# theremin.net
KiCad netlist of a schematic drawn in Altium Designer
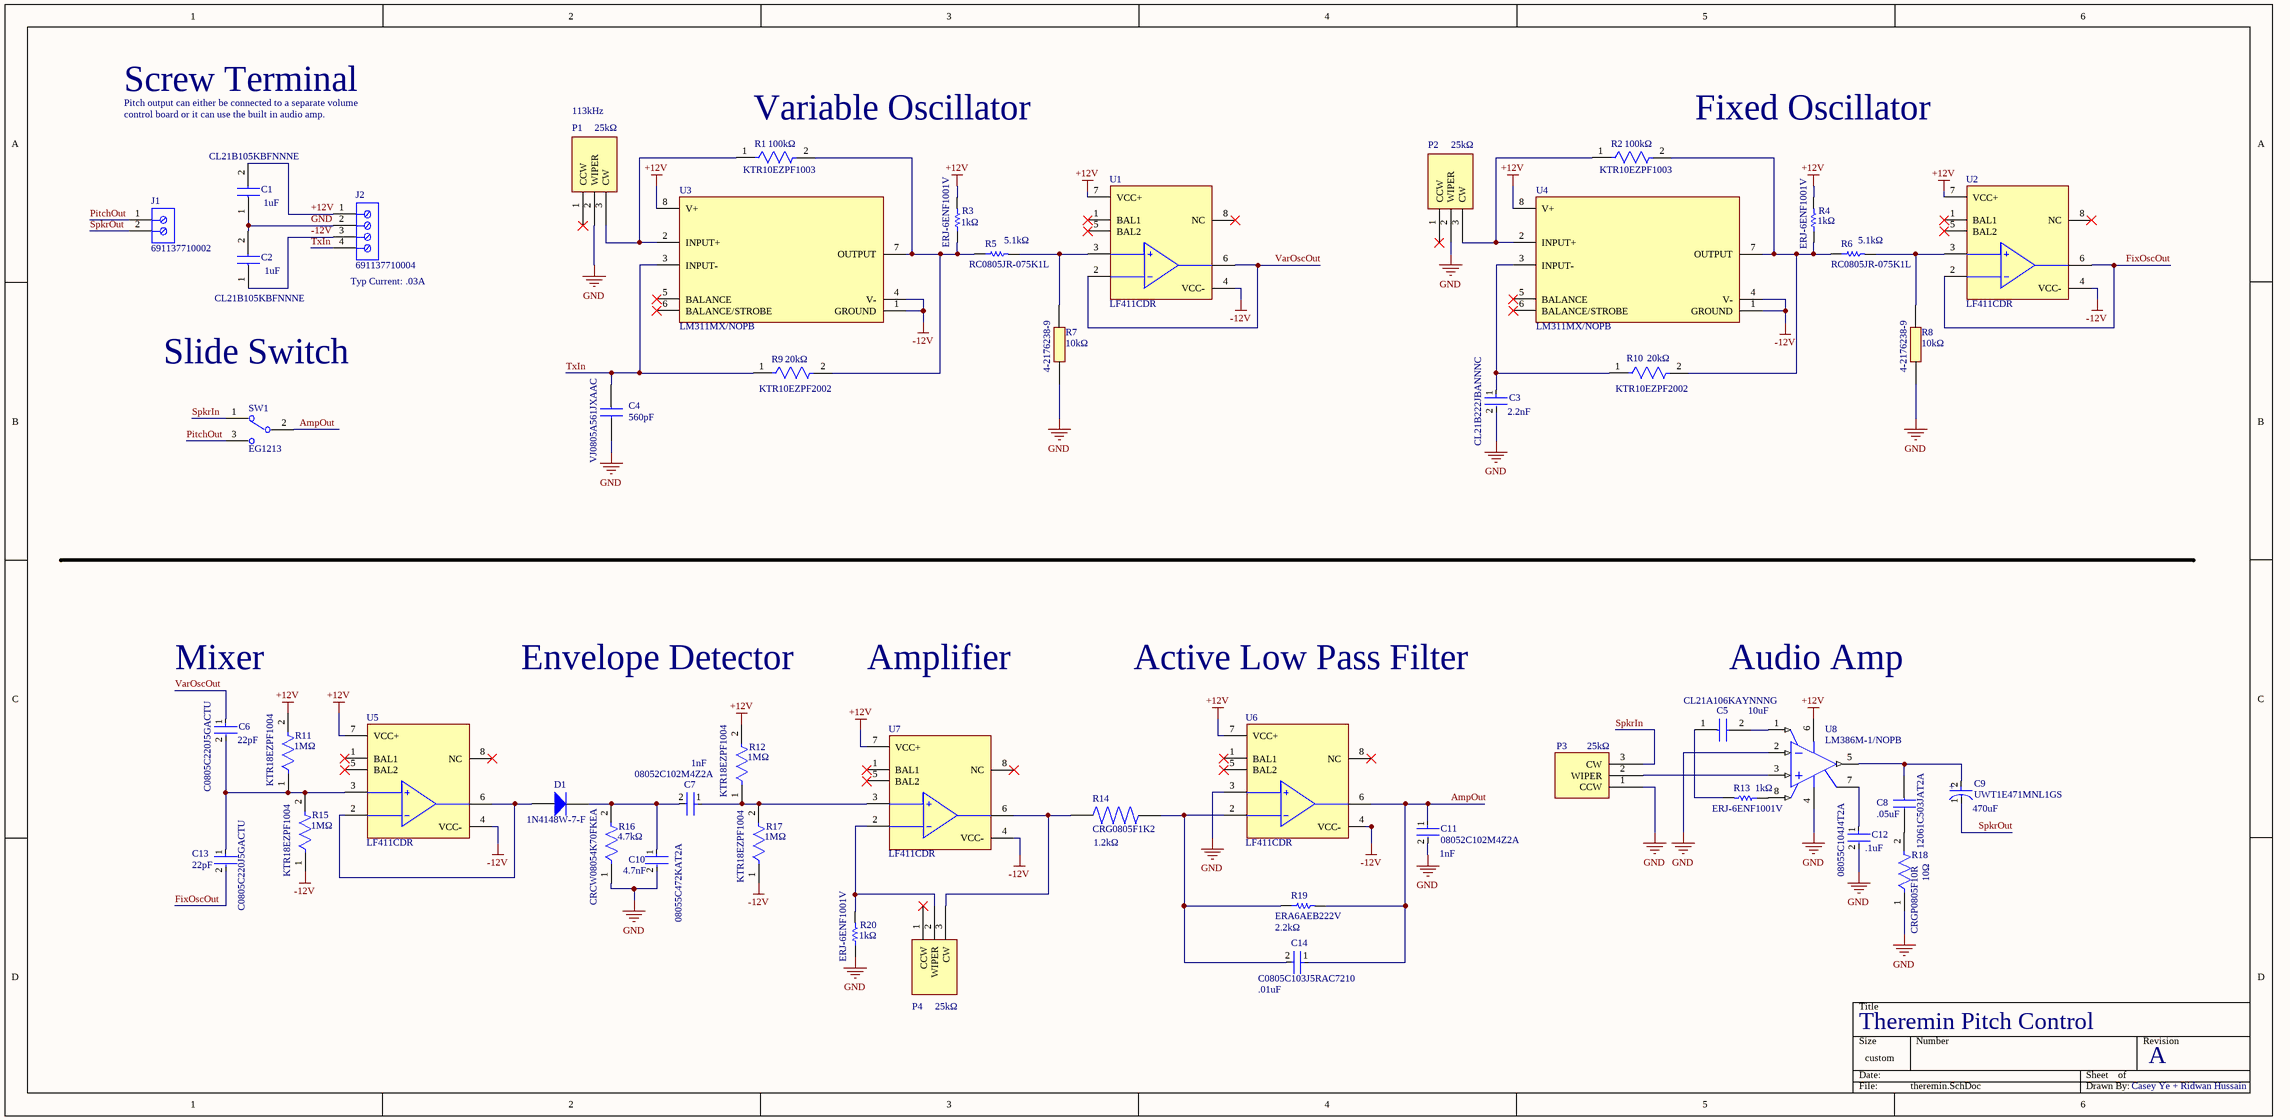
[diagram p0: theremin.SchDoc]

(export (version "E")
  (design (tool "Eeschema 10.0.6"))
  (components
    (comp (ref "C1")
      (value "CL21B105KBFNNNE")
      (footprint "SamacSys:CAPC2012X135N")
      (description "Capacitor")
      (fields (field (name "MOUSER PART NUMBER") "187-CL21B105KBFNNNE"))
      (libsource (lib "*") (part "CL21B105KBFNNNE"))
    )
    (comp (ref "C2")
      (value "CL21B105KBFNNNE")
      (footprint "SamacSys:CAPC2012X135N")
      (description "Capacitor")
      (fields (field (name "MOUSER PART NUMBER") "187-CL21B105KBFNNNE"))
      (libsource (lib "*") (part "CL21B105KBFNNNE"))
    )
    (comp (ref "C3")
      (value "CL21B222JBANNNC")
      (footprint "FP-CL21-IPC_B")
      (description "CL21 Series 0805 2.2nF 50V ±5% Tolerance X7R Multilayer Ceramic Chip Capacitor")
      (fields (field (name "TOLERANCE") "5%") (field (name "VOLTAGE") "50V"))
      (libsource (lib "Altium Content Vault") (part "b4654b650e69147ec39a6b967a45e02"))
    )
    (comp (ref "C4")
      (value "VJ0805A561JXAAC")
      (footprint "CAPC2012X145N")
      (description "VISHAY - VJ0805A561JXAAC - CAP, 560PF, 50V, 5%, C0G/NP0, 0805")
      (fields (field (name "MOUSER PART NUMBER") "77-VJ0805A561JXAAC"))
      (libsource (lib "PCB Lab - Cooper Union") (part "VJ0805A561JXAAC"))
    )
    (comp (ref "C5")
      (value "CL21A106KAYNNNG")
      (footprint "SamacSys:CAPC2012X145N")
      (description "Capacitor")
      (fields (field (name "MOUSER PART NUMBER") "187-CL21A106KAYNNNG"))
      (libsource (lib "*") (part "CL21A106KAYNNNG"))
    )
    (comp (ref "C6")
      (value "C0805C220J5GACTU")
      (footprint "FP-C0805C-DN-MFG")
      (description "Capacitor; Ceramic; Cap; 22.0pF; Tol 5%; SMT; Vol-Rtg 50V; C0G; Tape and Reel")
      (fields
        (field (name "OCTOPART") "https://octopart.com/c0805c220j5gactu-kemet-145470")
        (field (name "MANUFACTURER") "KEMET")
      )
      (libsource (lib "Altium Content Vault") (part "b4654b650e69147ec39a6b967a45e02"))
    )
    (comp (ref "C7")
      (value "08052C102M4Z2A")
      (footprint "FP-0805-L_2_01_0_2-W_1_25-IPC_B")
      (description "Automotive Ceramic Capacitor, 0805, 1nF, 20%, X7R, 0.15, 200V")
      (fields (field (name "TOLERANCE") "20%"))
      (libsource (lib "Altium Content Vault") (part "02cd4be3c70576c341d710602a673aa"))
    )
    (comp (ref "C8")
      (value "12061C503JAT2A")
      (footprint "CAPC3216X94N")
      (description "Multilayer Ceramic Capacitors MLCC - SMD/SMT 100V .05uF X7R 1206 5% Tol")
      (fields (field (name "MOUSER PART NUMBER") "581-12061C503JAT2A"))
      (libsource (lib "PCB Lab - Cooper Union") (part "12061C503JAT2A"))
    )
    (comp (ref "C9")
      (value "UWT1E471MNL1GS")
      (footprint "FP-UWT1E471MNL1GS-MFG")
      (description "CAP ALUM 470UF 20% 25V SMD")
      (fields (field (name "VOLTAGE") "25V") (field (name "TOLERANCE") "20%"))
      (libsource (lib "Altium Content Vault") (part "203bc49f2ac43e59fd269a8c329ed05"))
    )
    (comp (ref "C10")
      (value "08055C472KAT2A")
      (footprint "FP-0805-L_2_01_0_2-W_1_25-IPC_B")
      (description "General Purpose Ceramic Capacitor, 0805, 4.7nF, 10%, X7R, 0.15, 50V")
      (fields (field (name "VOLTAGE") "50V") (field (name "TOLERANCE") "10%"))
      (libsource (lib "Altium Content Vault") (part "02cd4be3c70576c341d710602a673aa"))
    )
    (comp (ref "C11")
      (value "08052C102M4Z2A")
      (footprint "FP-0805-L_2_01_0_2-W_1_25-IPC_B")
      (description "Automotive Ceramic Capacitor, 0805, 1nF, 20%, X7R, 0.15, 200V")
      (fields (field (name "TOLERANCE") "20%"))
      (libsource (lib "Altium Content Vault") (part "02cd4be3c70576c341d710602a673aa"))
    )
    (comp (ref "C12")
      (value "08055C104J4T2A")
      (footprint "FP-0805-L_2_01_0_2-W_1_25-MFG")
      (description "Automotive Ceramic Capacitor, 0805, 100nF, 5%, X7R, 15%, 50V")
      (fields (field (name "TOLERANCE") "5%"))
      (libsource (lib "Altium Content Vault") (part "02cd4be3c70576c341d710602a673aa"))
    )
    (comp (ref "C13")
      (value "C0805C220J5GACTU")
      (footprint "FP-C0805C-DN-MFG")
      (description "Capacitor; Ceramic; Cap; 22.0pF; Tol 5%; SMT; Vol-Rtg 50V; C0G; Tape and Reel")
      (fields
        (field (name "OCTOPART") "https://octopart.com/c0805c220j5gactu-kemet-145470")
        (field (name "MANUFACTURER") "KEMET")
      )
      (libsource (lib "Altium Content Vault") (part "b4654b650e69147ec39a6b967a45e02"))
    )
    (comp (ref "C14")
      (value "C0805C103J5RAC7210")
      (footprint "FP-C0805C-DN-MFG")
      (description "CAP CER SMD 0805 .01UF X7R 5% 50")
      (fields
        (field (name "MANUFACTURER") "KEMET")
        (field (name "OCTOPART") "https://octopart.com/c0805c103j5rac7210-kemet-3921106")
      )
      (libsource (lib "Altium Content Vault") (part "b4654b650e69147ec39a6b967a45e02"))
    )
    (comp (ref "D1")
      (value "1N4148W-7-F")
      (footprint "DIOD-SOD123-2_V")
      (description "Fast Switching Diode, 100 V, 0.15 A, -65 to 150 degC, 2-Pin?SOD123, RoHS, Tape and Reel")
      (fields (field (name "MANUFACTURER") "DiodesIncorporated"))
      (libsource (lib "Altium Content Vault") (part "D-AK-2"))
    )
    (comp (ref "J1")
      (value "691137710002")
      (footprint "691137710002")
      (libsource (lib "Altium Content Vault") (part "TBL - 1R - 02P - Screw"))
    )
    (comp (ref "J2")
      (value "691137710004")
      (footprint "691137710004")
      (libsource (lib "Altium Content Vault") (part "TBL - 1R - 04P - Screw"))
    )
    (comp (ref "P1")
      (value "25kOhmPotentiometer")
      (footprint "25kOhmPotentiometer-Footprint-1")
      (description "25k Ohm Potentiometer")
      (libsource (lib "") (part "25kOhmPotentiometer_1"))
    )
    (comp (ref "P2")
      (value "25kOhmPotentiometer")
      (footprint "25kOhmPotentiometer-Footprint-1")
      (description "25k Ohm Potentiometer")
      (libsource (lib "") (part "25kOhmPotentiometer_1"))
    )
    (comp (ref "P3")
      (value "25kOhmPotentiometer")
      (footprint "25kOhmPotentiometer-Footprint-1")
      (description "25k Ohm Potentiometer")
      (libsource (lib "PCB Lab - Cooper Union") (part "25kOhmPotentiometer"))
    )
    (comp (ref "P4")
      (value "25kOhmPotentiometer")
      (footprint "25kOhmPotentiometer-Footprint-1")
      (description "25k Ohm Potentiometer")
      (libsource (lib "PCB Lab - Cooper Union") (part "25kOhmPotentiometer"))
    )
    (comp (ref "R1")
      (value "KTR10EZPF1003")
      (footprint "FP-KTR10-MFG")
      (description "Res Thick Film 0805 100kΩ 1% 0.125W ±100ppm/°C Automotive Paper T/R")
      (fields (field (name "TOLERANCE") "1%"))
      (libsource (lib "Altium Content Vault") (part "1029c3af85768c4190bb7ad29bc67b5"))
    )
    (comp (ref "R2")
      (value "KTR10EZPF1003")
      (footprint "FP-KTR10-MFG")
      (description "Res Thick Film 0805 100kΩ 1% 0.125W ±100ppm/°C Automotive Paper T/R")
      (fields (field (name "TOLERANCE") "1%"))
      (libsource (lib "Altium Content Vault") (part "1029c3af85768c4190bb7ad29bc67b5"))
    )
    (comp (ref "R3")
      (value "ERJ-6ENF1001V")
      (footprint "RESC2013X70X40ML20T20")
      (description "Chip Resistor, 1 KOhm, +/- 1%, 0.125 W, -55 to 155 degC, 0805 (2012 Metric), RoHS, Tape and Reel")
      (fields (field (name "MANUFACTURER") "Panasonic"))
      (libsource (lib "Altium Content Vault") (part "RES-2"))
    )
    (comp (ref "R4")
      (value "ERJ-6ENF1001V")
      (footprint "RESC2013X70X40ML20T20")
      (description "Chip Resistor, 1 KOhm, +/- 1%, 0.125 W, -55 to 155 degC, 0805 (2012 Metric), RoHS, Tape and Reel")
      (fields (field (name "MANUFACTURER") "Panasonic"))
      (libsource (lib "Altium Content Vault") (part "RES-2"))
    )
    (comp (ref "R5")
      (value "RC0805JR-075K1L")
      (footprint "RESC2013X60X35ML10T20")
      (fields (field (name "MANUFACTURER") "Yageo"))
      (libsource (lib "Altium Content Vault") (part "RES"))
    )
    (comp (ref "R6")
      (value "RC0805JR-075K1L")
      (footprint "RESC2013X60X35ML10T20")
      (fields (field (name "MANUFACTURER") "Yageo"))
      (libsource (lib "Altium Content Vault") (part "RES"))
    )
    (comp (ref "R7")
      (value "4-2176238-9")
      (footprint "RESC2012X65N")
      (description "Thin Film Resistors - SMD CPF A 0805 10K 0.1% 25PPM 5K RL")
      (libsource (lib "PCB Lab - Cooper Union") (part "4-2176238-9"))
    )
    (comp (ref "R8")
      (value "4-2176238-9")
      (footprint "RESC2012X65N")
      (description "Thin Film Resistors - SMD CPF A 0805 10K 0.1% 25PPM 5K RL")
      (libsource (lib "PCB Lab - Cooper Union") (part "4-2176238-9"))
    )
    (comp (ref "R9")
      (value "KTR10EZPF2002")
      (footprint "FP-KTR10-IPC_C")
      (description "Res Thick Film 0805 20kΩ 1% 0.125W ±100ppm/°C Automotive Paper T/R")
      (fields (field (name "TOLERANCE") "1%"))
      (libsource (lib "Altium Content Vault") (part "1029c3af85768c4190bb7ad29bc67b5"))
    )
    (comp (ref "R10")
      (value "KTR10EZPF2002")
      (footprint "FP-KTR10-IPC_C")
      (description "Res Thick Film 0805 20kΩ 1% 0.125W ±100ppm/°C Automotive Paper T/R")
      (fields (field (name "TOLERANCE") "1%"))
      (libsource (lib "Altium Content Vault") (part "1029c3af85768c4190bb7ad29bc67b5"))
    )
    (comp (ref "R11")
      (value "KTR18EZPF1004")
      (footprint "FP-KTR18-IPC_C")
      (description "Res Thick Film 1206 1MΩ 1% 0.1W ±100ppm/°C Automotive Paper T/R")
      (fields (field (name "TOLERANCE") "1%"))
      (libsource (lib "Altium Content Vault") (part "1029c3af85768c4190bb7ad29bc67b5"))
    )
    (comp (ref "R12")
      (value "KTR18EZPF1004")
      (footprint "FP-KTR18-IPC_C")
      (description "Res Thick Film 1206 1MΩ 1% 0.1W ±100ppm/°C Automotive Paper T/R")
      (fields (field (name "TOLERANCE") "1%"))
      (libsource (lib "Altium Content Vault") (part "1029c3af85768c4190bb7ad29bc67b5"))
    )
    (comp (ref "R13")
      (value "ERJ-6ENF1001V")
      (footprint "RESC2013X70X40ML20T20")
      (description "Chip Resistor, 1 KOhm, +/- 1%, 0.125 W, -55 to 155 degC, 0805 (2012 Metric), RoHS, Tape and Reel")
      (fields (field (name "MANUFACTURER") "Panasonic"))
      (libsource (lib "Altium Content Vault") (part "RES-2"))
    )
    (comp (ref "R14")
      (value "CRG0805F1K2")
      (footprint "RESC2012X65N")
      (description "Fixed Resistors")
      (fields (field (name "MF") "TE Connectivity") (field (name "TOLERANCE") "1%"))
      (libsource (lib "PCB Lab - Cooper Union") (part "CRG0805F1K2"))
    )
    (comp (ref "R15")
      (value "KTR18EZPF1004")
      (footprint "FP-KTR18-IPC_C")
      (description "Res Thick Film 1206 1MΩ 1% 0.1W ±100ppm/°C Automotive Paper T/R")
      (fields (field (name "TOLERANCE") "1%"))
      (libsource (lib "Altium Content Vault") (part "1029c3af85768c4190bb7ad29bc67b5"))
    )
    (comp (ref "R16")
      (value "CRCW08054K70FKEA")
      (footprint "FP-CRCW0805-e3-IPC_B")
      (description "RES Thick Film, 4.7kΩ, 1%, 0.125W, 100ppm/°C, 0805")
      (fields (field (name "TOLERANCE") "1%"))
      (libsource (lib "Altium Content Vault") (part "1029c3af85768c4190bb7ad29bc67b5"))
    )
    (comp (ref "R17")
      (value "KTR18EZPF1004")
      (footprint "FP-KTR18-IPC_C")
      (description "Res Thick Film 1206 1MΩ 1% 0.1W ±100ppm/°C Automotive Paper T/R")
      (fields (field (name "TOLERANCE") "1%"))
      (libsource (lib "Altium Content Vault") (part "1029c3af85768c4190bb7ad29bc67b5"))
    )
    (comp (ref "R18")
      (value "CRGP0805F10R")
      (footprint "FP-CRGP0805-IPC_C")
      (description "CRGP 0805 10R 1%")
      (fields (field (name "TOLERANCE") "0.01") (field (name "MANUFACTURER") "TE"))
      (libsource (lib "Altium Content Vault") (part "1029c3af85768c4190bb7ad29bc67b5"))
    )
    (comp (ref "R19")
      (value "ERA6AEB222V")
      (footprint "RESC2013X60X40LL20T25")
      (fields (field (name "MANUFACTURER") "Panasonic"))
      (libsource (lib "Altium Content Vault") (part "RES"))
    )
    (comp (ref "R20")
      (value "ERJ-6ENF1001V")
      (footprint "RESC2013X70X40ML20T20")
      (description "Chip Resistor, 1 KOhm, +/- 1%, 0.125 W, -55 to 155 degC, 0805 (2012 Metric), RoHS, Tape and Reel")
      (fields (field (name "MANUFACTURER") "Panasonic"))
      (libsource (lib "Altium Content Vault") (part "RES-2"))
    )
    (comp (ref "SW1")
      (value "EG1213")
      (footprint "SW_EG1213")
      (description "<b>EG Series SPDT On-On Right Angle Through Hole Slide Switch</b>")
      (libsource (lib "PCB Lab - Cooper Union") (part "EG1213"))
    )
    (comp (ref "U1")
      (value "LF411CDR")
      (footprint "FP-D0008A-IPC_A")
      (description "IC OPAMP JFET 1 CIRCUIT 8SOIC")
      (libsource (lib "Altium Content Vault") (part "9f678137a5b34a83ff501496c3bb5e5"))
    )
    (comp (ref "U2")
      (value "LF411CDR")
      (footprint "FP-D0008A-IPC_A")
      (description "IC OPAMP JFET 1 CIRCUIT 8SOIC")
      (libsource (lib "Altium Content Vault") (part "9f678137a5b34a83ff501496c3bb5e5"))
    )
    (comp (ref "U3")
      (value "LM311MX/NOPB")
      (footprint "FP-D0008A-IPC_A")
      (description "IC VOLTAGE COMPARATOR 8-SOIC")
      (libsource (lib "Altium Content Vault") (part "b63dbd1a96c31a20977de8dc8ac0a99"))
    )
    (comp (ref "U4")
      (value "LM311MX/NOPB")
      (footprint "FP-D0008A-IPC_A")
      (description "IC VOLTAGE COMPARATOR 8-SOIC")
      (libsource (lib "Altium Content Vault") (part "b63dbd1a96c31a20977de8dc8ac0a99"))
    )
    (comp (ref "U5")
      (value "LF411CDR")
      (footprint "FP-D0008A-IPC_A")
      (description "IC OPAMP JFET 1 CIRCUIT 8SOIC")
      (libsource (lib "Altium Content Vault") (part "9f678137a5b34a83ff501496c3bb5e5"))
    )
    (comp (ref "U6")
      (value "LF411CDR")
      (footprint "FP-D0008A-IPC_A")
      (description "IC OPAMP JFET 1 CIRCUIT 8SOIC")
      (libsource (lib "Altium Content Vault") (part "9f678137a5b34a83ff501496c3bb5e5"))
    )
    (comp (ref "U7")
      (value "LF411CDR")
      (footprint "FP-D0008A-IPC_A")
      (description "IC OPAMP JFET 1 CIRCUIT 8SOIC")
      (libsource (lib "Altium Content Vault") (part "9f678137a5b34a83ff501496c3bb5e5"))
    )
    (comp (ref "U8")
      (value "LM386M-1/NOPB")
      (footprint "TI-D8_M")
      (description "Low Voltage Audio Power Amplifier, 0 to 70 degC, 8-pin SOIC (D8), Green (RoHS & no Sb/Br)")
      (fields (field (name "MANUFACTURER") "Texas Instruments"))
      (libsource (lib "Altium Content Vault") (part "TI-LM386undefined"))
    )
  )
  (nets
    (net (code "1") (name "+12V") (class "Default")
      (node (ref "C1") (pin "2") (pinfunction "2_2") (pintype "passive"))
      (node (ref "J2") (pin "1") (pinfunction "1_1") (pintype "passive"))
      (node (ref "R11") (pin "2") (pinfunction "2_2") (pintype "passive"))
      (node (ref "R12") (pin "2") (pinfunction "2_2") (pintype "passive"))
      (node (ref "R3") (pin "2") (pinfunction "2_2") (pintype "passive"))
      (node (ref "R4") (pin "2") (pinfunction "2_2") (pintype "passive"))
      (node (ref "U1") (pin "7") (pinfunction "VCC+_7") (pintype "power_in"))
      (node (ref "U2") (pin "7") (pinfunction "VCC+_7") (pintype "power_in"))
      (node (ref "U3") (pin "8") (pinfunction "V+_8") (pintype "power_in"))
      (node (ref "U4") (pin "8") (pinfunction "V+_8") (pintype "power_in"))
      (node (ref "U5") (pin "7") (pinfunction "VCC+_7") (pintype "power_in"))
      (node (ref "U6") (pin "7") (pinfunction "VCC+_7") (pintype "power_in"))
      (node (ref "U7") (pin "7") (pinfunction "VCC+_7") (pintype "power_in"))
      (node (ref "U8") (pin "6") (pinfunction "VS_6") (pintype "power_in"))
    )
    (net (code "2") (name "-12V") (class "Default")
      (node (ref "C2") (pin "1") (pinfunction "1_1") (pintype "passive"))
      (node (ref "J2") (pin "3") (pinfunction "3_3") (pintype "passive"))
      (node (ref "R15") (pin "1") (pinfunction "1_1") (pintype "passive"))
      (node (ref "R17") (pin "1") (pinfunction "1_1") (pintype "passive"))
      (node (ref "U1") (pin "4") (pinfunction "VCC-_4") (pintype "power_in"))
      (node (ref "U2") (pin "4") (pinfunction "VCC-_4") (pintype "power_in"))
      (node (ref "U3") (pin "1") (pinfunction "GROUND_1") (pintype "power_in"))
      (node (ref "U3") (pin "4") (pinfunction "V-_4") (pintype "power_in"))
      (node (ref "U4") (pin "1") (pinfunction "GROUND_1") (pintype "power_in"))
      (node (ref "U4") (pin "4") (pinfunction "V-_4") (pintype "power_in"))
      (node (ref "U5") (pin "4") (pinfunction "VCC-_4") (pintype "power_in"))
      (node (ref "U6") (pin "4") (pinfunction "VCC-_4") (pintype "power_in"))
      (node (ref "U7") (pin "4") (pinfunction "VCC-_4") (pintype "power_in"))
    )
    (net (code "3") (name "/AmpOut") (class "Default")
      (node (ref "C11") (pin "1") (pinfunction "1_1") (pintype "passive"))
      (node (ref "C14") (pin "1") (pinfunction "1_1") (pintype "passive"))
      (node (ref "R19") (pin "2") (pinfunction "2_2") (pintype "passive"))
      (node (ref "SW1") (pin "2") (pinfunction "2_2") (pintype "passive"))
      (node (ref "U6") (pin "6") (pinfunction "OUT_6") (pintype "passive"))
    )
    (net (code "4") (name "/FixOscOut") (class "Default")
      (node (ref "C13") (pin "2") (pinfunction "2_2") (pintype "passive"))
      (node (ref "U2") (pin "2") (pinfunction "IN-_2") (pintype "tri_state"))
      (node (ref "U2") (pin "6") (pinfunction "OUT_6") (pintype "passive"))
    )
    (net (code "5") (name "/PitchOut") (class "Default")
      (node (ref "J1") (pin "1") (pinfunction "1_1") (pintype "passive"))
      (node (ref "SW1") (pin "3") (pinfunction "3_3") (pintype "passive"))
    )
    (net (code "6") (name "/SpkrIn") (class "Default")
      (node (ref "P3") (pin "3") (pinfunction "CW_3") (pintype "passive"))
      (node (ref "SW1") (pin "1") (pinfunction "1_1") (pintype "passive"))
    )
    (net (code "7") (name "/SpkrOut") (class "Default")
      (node (ref "C9") (pin "1") (pinfunction "C_1") (pintype "passive"))
      (node (ref "J1") (pin "2") (pinfunction "2_2") (pintype "passive"))
    )
    (net (code "8") (name "/TxIn") (class "Default")
      (node (ref "C4") (pin "2") (pinfunction "2_2") (pintype "passive"))
      (node (ref "J2") (pin "4") (pinfunction "4_4") (pintype "passive"))
      (node (ref "R9") (pin "1") (pinfunction "1_1") (pintype "passive"))
      (node (ref "U3") (pin "3") (pinfunction "INPUT-_3") (pintype "tri_state"))
    )
    (net (code "9") (name "/VarOscOut") (class "Default")
      (node (ref "C6") (pin "1") (pinfunction "1_1") (pintype "passive"))
      (node (ref "U1") (pin "2") (pinfunction "IN-_2") (pintype "tri_state"))
      (node (ref "U1") (pin "6") (pinfunction "OUT_6") (pintype "passive"))
    )
    (net (code "10") (name "GND") (class "Default")
      (node (ref "C1") (pin "1") (pinfunction "1_1") (pintype "passive"))
      (node (ref "C10") (pin "2") (pinfunction "2_2") (pintype "passive"))
      (node (ref "C11") (pin "2") (pinfunction "2_2") (pintype "passive"))
      (node (ref "C12") (pin "2") (pinfunction "2_2") (pintype "passive"))
      (node (ref "C2") (pin "2") (pinfunction "2_2") (pintype "passive"))
      (node (ref "C3") (pin "2") (pinfunction "2_2") (pintype "passive"))
      (node (ref "C4") (pin "1") (pinfunction "1_1") (pintype "passive"))
      (node (ref "J2") (pin "2") (pinfunction "2_2") (pintype "passive"))
      (node (ref "P1") (pin "2") (pinfunction "WIPER_2") (pintype "passive"))
      (node (ref "P2") (pin "2") (pinfunction "WIPER_2") (pintype "passive"))
      (node (ref "P3") (pin "1") (pinfunction "CCW_1") (pintype "passive"))
      (node (ref "R16") (pin "1") (pinfunction "1_1") (pintype "passive"))
      (node (ref "R18") (pin "1") (pinfunction "1_1") (pintype "passive"))
      (node (ref "R20") (pin "1") (pinfunction "1_1") (pintype "passive"))
      (node (ref "R7") (pin "1") (pinfunction "1_1") (pintype "passive"))
      (node (ref "R8") (pin "1") (pinfunction "1_1") (pintype "passive"))
      (node (ref "U6") (pin "3") (pinfunction "IN+_3") (pintype "tri_state"))
      (node (ref "U8") (pin "2") (pinfunction "IN-_2") (pintype "input"))
      (node (ref "U8") (pin "4") (pinfunction "GND_4") (pintype "power_in"))
    )
    (net (code "11") (name "Net-(C5-Pad1)") (class "Default")
      (node (ref "C5") (pin "1") (pinfunction "1_1") (pintype "passive"))
      (node (ref "R13") (pin "2") (pinfunction "2_2") (pintype "passive"))
    )
    (net (code "12") (name "Net-(C5-Pad2)") (class "Default")
      (node (ref "C5") (pin "2") (pinfunction "2_2") (pintype "passive"))
      (node (ref "U8") (pin "1") (pinfunction "GAIN_1") (pintype "input"))
    )
    (net (code "13") (name "Net-(C8-Pad1)") (class "Default")
      (node (ref "C8") (pin "1") (pinfunction "1_1") (pintype "passive"))
      (node (ref "R18") (pin "2") (pinfunction "2_2") (pintype "passive"))
    )
    (net (code "14") (name "Net-(C9-A)") (class "Default")
      (node (ref "C8") (pin "2") (pinfunction "2_2") (pintype "passive"))
      (node (ref "C9") (pin "2") (pinfunction "A_2") (pintype "passive"))
      (node (ref "U8") (pin "5") (pinfunction "VOUT_5") (pintype "output"))
    )
    (net (code "15") (name "Net-(D1-A)") (class "Default")
      (node (ref "D1") (pin "1") (pinfunction "A_1") (pintype "passive"))
      (node (ref "U5") (pin "2") (pinfunction "IN-_2") (pintype "tri_state"))
      (node (ref "U5") (pin "6") (pinfunction "OUT_6") (pintype "passive"))
    )
    (net (code "16") (name "Net-(D1-K)") (class "Default")
      (node (ref "C10") (pin "1") (pinfunction "1_1") (pintype "passive"))
      (node (ref "C7") (pin "2") (pinfunction "2_2") (pintype "passive"))
      (node (ref "D1") (pin "2") (pinfunction "K_2") (pintype "passive"))
      (node (ref "R16") (pin "2") (pinfunction "2_2") (pintype "passive"))
    )
    (net (code "17") (name "Net-(P1-CW)") (class "Default")
      (node (ref "P1") (pin "3") (pinfunction "CW_3") (pintype "passive"))
      (node (ref "R1") (pin "1") (pinfunction "1_1") (pintype "passive"))
      (node (ref "U3") (pin "2") (pinfunction "INPUT+_2") (pintype "tri_state"))
    )
    (net (code "18") (name "Net-(P2-CW)") (class "Default")
      (node (ref "P2") (pin "3") (pinfunction "CW_3") (pintype "passive"))
      (node (ref "R2") (pin "1") (pinfunction "1_1") (pintype "passive"))
      (node (ref "U4") (pin "2") (pinfunction "INPUT+_2") (pintype "tri_state"))
    )
    (net (code "19") (name "Net-(P3-WIPER)") (class "Default")
      (node (ref "P3") (pin "2") (pinfunction "WIPER_2") (pintype "passive"))
      (node (ref "U8") (pin "3") (pinfunction "IN+_3") (pintype "input"))
    )
    (net (code "20") (name "Net-(P4-CW)") (class "Default")
      (node (ref "P4") (pin "3") (pinfunction "CW_3") (pintype "passive"))
      (node (ref "R14") (pin "1") (pinfunction "1_1") (pintype "passive"))
      (node (ref "U7") (pin "6") (pinfunction "OUT_6") (pintype "passive"))
    )
    (net (code "21") (name "Net-(P4-WIPER)") (class "Default")
      (node (ref "P4") (pin "2") (pinfunction "WIPER_2") (pintype "passive"))
      (node (ref "R20") (pin "2") (pinfunction "2_2") (pintype "passive"))
      (node (ref "U7") (pin "2") (pinfunction "IN-_2") (pintype "tri_state"))
    )
    (net (code "22") (name "Net-(R13-Pad1)") (class "Default")
      (node (ref "R13") (pin "1") (pinfunction "1_1") (pintype "passive"))
      (node (ref "U8") (pin "8") (pinfunction "GAIN_8") (pintype "input"))
    )
    (net (code "23") (name "Net-(U1-IN+)") (class "Default")
      (node (ref "R5") (pin "2") (pinfunction "2_2") (pintype "passive"))
      (node (ref "R7") (pin "2") (pinfunction "2_2") (pintype "passive"))
      (node (ref "U1") (pin "3") (pinfunction "IN+_3") (pintype "tri_state"))
    )
    (net (code "24") (name "Net-(U2-IN+)") (class "Default")
      (node (ref "R6") (pin "2") (pinfunction "2_2") (pintype "passive"))
      (node (ref "R8") (pin "2") (pinfunction "2_2") (pintype "passive"))
      (node (ref "U2") (pin "3") (pinfunction "IN+_3") (pintype "tri_state"))
    )
    (net (code "25") (name "Net-(U3-OUTPUT)") (class "Default")
      (node (ref "R1") (pin "2") (pinfunction "2_2") (pintype "passive"))
      (node (ref "R3") (pin "1") (pinfunction "1_1") (pintype "passive"))
      (node (ref "R5") (pin "1") (pinfunction "1_1") (pintype "passive"))
      (node (ref "R9") (pin "2") (pinfunction "2_2") (pintype "passive"))
      (node (ref "U3") (pin "7") (pinfunction "OUTPUT_7") (pintype "open_collector"))
    )
    (net (code "26") (name "Net-(U4-INPUT-)") (class "Default")
      (node (ref "C3") (pin "1") (pinfunction "1_1") (pintype "passive"))
      (node (ref "R10") (pin "1") (pinfunction "1_1") (pintype "passive"))
      (node (ref "U4") (pin "3") (pinfunction "INPUT-_3") (pintype "tri_state"))
    )
    (net (code "27") (name "Net-(U4-OUTPUT)") (class "Default")
      (node (ref "R10") (pin "2") (pinfunction "2_2") (pintype "passive"))
      (node (ref "R2") (pin "2") (pinfunction "2_2") (pintype "passive"))
      (node (ref "R4") (pin "1") (pinfunction "1_1") (pintype "passive"))
      (node (ref "R6") (pin "1") (pinfunction "1_1") (pintype "passive"))
      (node (ref "U4") (pin "7") (pinfunction "OUTPUT_7") (pintype "open_collector"))
    )
    (net (code "28") (name "Net-(U5-IN+)") (class "Default")
      (node (ref "C13") (pin "1") (pinfunction "1_1") (pintype "passive"))
      (node (ref "C6") (pin "2") (pinfunction "2_2") (pintype "passive"))
      (node (ref "R11") (pin "1") (pinfunction "1_1") (pintype "passive"))
      (node (ref "R15") (pin "2") (pinfunction "2_2") (pintype "passive"))
      (node (ref "U5") (pin "3") (pinfunction "IN+_3") (pintype "tri_state"))
    )
    (net (code "29") (name "Net-(U6-IN-)") (class "Default")
      (node (ref "C14") (pin "2") (pinfunction "2_2") (pintype "passive"))
      (node (ref "R14") (pin "2") (pinfunction "2_2") (pintype "passive"))
      (node (ref "R19") (pin "1") (pinfunction "1_1") (pintype "passive"))
      (node (ref "U6") (pin "2") (pinfunction "IN-_2") (pintype "tri_state"))
    )
    (net (code "30") (name "Net-(U7-IN+)") (class "Default")
      (node (ref "C7") (pin "1") (pinfunction "1_1") (pintype "passive"))
      (node (ref "R12") (pin "1") (pinfunction "1_1") (pintype "passive"))
      (node (ref "R17") (pin "2") (pinfunction "2_2") (pintype "passive"))
      (node (ref "U7") (pin "3") (pinfunction "IN+_3") (pintype "tri_state"))
    )
    (net (code "31") (name "Net-(U8-BYPASS)") (class "Default")
      (node (ref "C12") (pin "1") (pinfunction "1_1") (pintype "passive"))
      (node (ref "U8") (pin "7") (pinfunction "BYPASS_7") (pintype "passive"))
    )
    (net (code "32") (name "unconnected-(P1-CCW-Pad1)") (class "Default")
      (node (ref "P1") (pin "1") (pinfunction "CCW_1") (pintype "passive+no_connect"))
    )
    (net (code "33") (name "unconnected-(P2-CCW-Pad1)") (class "Default")
      (node (ref "P2") (pin "1") (pinfunction "CCW_1") (pintype "passive+no_connect"))
    )
    (net (code "34") (name "unconnected-(P4-CCW-Pad1)") (class "Default")
      (node (ref "P4") (pin "1") (pinfunction "CCW_1") (pintype "passive+no_connect"))
    )
    (net (code "35") (name "unconnected-(U1-BAL1-Pad1)") (class "Default")
      (node (ref "U1") (pin "1") (pinfunction "BAL1_1") (pintype "passive+no_connect"))
    )
    (net (code "36") (name "unconnected-(U1-BAL2-Pad5)") (class "Default")
      (node (ref "U1") (pin "5") (pinfunction "BAL2_5") (pintype "passive+no_connect"))
    )
    (net (code "37") (name "unconnected-(U1-NC-Pad8)") (class "Default")
      (node (ref "U1") (pin "8") (pinfunction "NC_8") (pintype "passive+no_connect"))
    )
    (net (code "38") (name "unconnected-(U2-BAL1-Pad1)") (class "Default")
      (node (ref "U2") (pin "1") (pinfunction "BAL1_1") (pintype "passive+no_connect"))
    )
    (net (code "39") (name "unconnected-(U2-BAL2-Pad5)") (class "Default")
      (node (ref "U2") (pin "5") (pinfunction "BAL2_5") (pintype "passive+no_connect"))
    )
    (net (code "40") (name "unconnected-(U2-NC-Pad8)") (class "Default")
      (node (ref "U2") (pin "8") (pinfunction "NC_8") (pintype "passive+no_connect"))
    )
    (net (code "41") (name "unconnected-(U3-BALANCE-Pad5)") (class "Default")
      (node (ref "U3") (pin "5") (pinfunction "BALANCE_5") (pintype "passive+no_connect"))
    )
    (net (code "42") (name "unconnected-(U3-BALANCE{slash}STROBE-Pad6)") (class "Default")
      (node (ref "U3") (pin "6") (pinfunction "BALANCE/STROBE_6") (pintype "passive+no_connect"))
    )
    (net (code "43") (name "unconnected-(U4-BALANCE-Pad5)") (class "Default")
      (node (ref "U4") (pin "5") (pinfunction "BALANCE_5") (pintype "passive+no_connect"))
    )
    (net (code "44") (name "unconnected-(U4-BALANCE{slash}STROBE-Pad6)") (class "Default")
      (node (ref "U4") (pin "6") (pinfunction "BALANCE/STROBE_6") (pintype "passive+no_connect"))
    )
    (net (code "45") (name "unconnected-(U5-BAL1-Pad1)") (class "Default")
      (node (ref "U5") (pin "1") (pinfunction "BAL1_1") (pintype "passive+no_connect"))
    )
    (net (code "46") (name "unconnected-(U5-BAL2-Pad5)") (class "Default")
      (node (ref "U5") (pin "5") (pinfunction "BAL2_5") (pintype "passive+no_connect"))
    )
    (net (code "47") (name "unconnected-(U5-NC-Pad8)") (class "Default")
      (node (ref "U5") (pin "8") (pinfunction "NC_8") (pintype "passive+no_connect"))
    )
    (net (code "48") (name "unconnected-(U6-BAL1-Pad1)") (class "Default")
      (node (ref "U6") (pin "1") (pinfunction "BAL1_1") (pintype "passive+no_connect"))
    )
    (net (code "49") (name "unconnected-(U6-BAL2-Pad5)") (class "Default")
      (node (ref "U6") (pin "5") (pinfunction "BAL2_5") (pintype "passive+no_connect"))
    )
    (net (code "50") (name "unconnected-(U6-NC-Pad8)") (class "Default")
      (node (ref "U6") (pin "8") (pinfunction "NC_8") (pintype "passive+no_connect"))
    )
    (net (code "51") (name "unconnected-(U7-BAL1-Pad1)") (class "Default")
      (node (ref "U7") (pin "1") (pinfunction "BAL1_1") (pintype "passive+no_connect"))
    )
    (net (code "52") (name "unconnected-(U7-BAL2-Pad5)") (class "Default")
      (node (ref "U7") (pin "5") (pinfunction "BAL2_5") (pintype "passive+no_connect"))
    )
    (net (code "53") (name "unconnected-(U7-NC-Pad8)") (class "Default")
      (node (ref "U7") (pin "8") (pinfunction "NC_8") (pintype "passive+no_connect"))
    )
  )
)
